# TransientsWiring.net
KiCad netlist of a schematic drawn in EAGLE
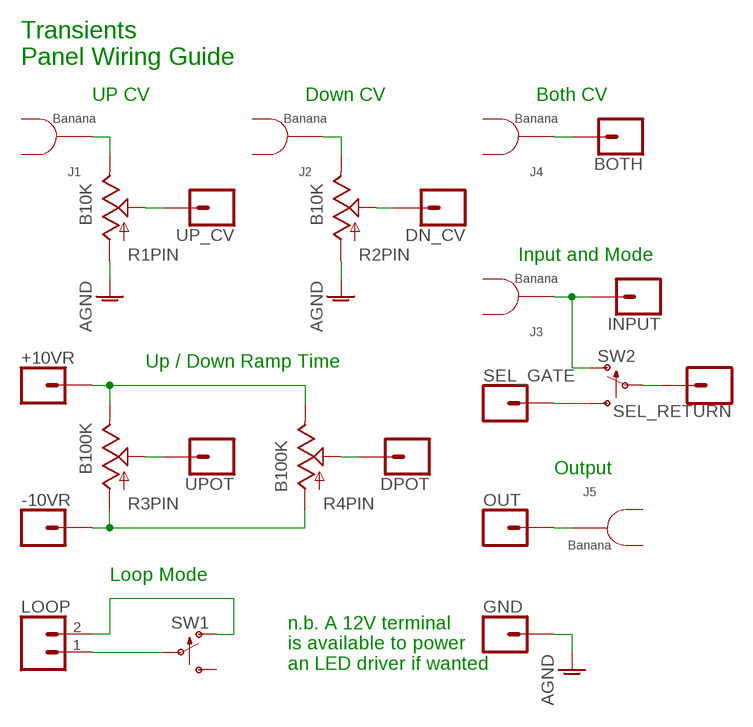
[diagram p0: schematic, sheet 1]

(export (version "E")
  (design (tool "Eeschema 10.0.6"))
  (components
    (comp (ref "+10VR")
      (value "1XWIREPAD")
      (footprint "eagle-import:1X01")
      (libsource (lib "eagle-import") (part "1XWIREPAD"))
    )
    (comp (ref "-10VR")
      (value "1XWIREPAD")
      (footprint "eagle-import:1X01")
      (libsource (lib "eagle-import") (part "1XWIREPAD"))
    )
    (comp (ref "BOTH")
      (value "1XWIREPAD")
      (footprint "eagle-import:1X01")
      (libsource (lib "eagle-import") (part "1XWIREPAD"))
    )
    (comp (ref "DN_CV")
      (value "1XWIREPAD")
      (footprint "eagle-import:1X01")
      (libsource (lib "eagle-import") (part "1XWIREPAD"))
    )
    (comp (ref "DPOT")
      (value "1XWIREPAD")
      (footprint "eagle-import:1X01")
      (libsource (lib "eagle-import") (part "1XWIREPAD"))
    )
    (comp (ref "GND")
      (value "1XWIREPAD")
      (footprint "eagle-import:1X01")
      (libsource (lib "eagle-import") (part "1XWIREPAD"))
    )
    (comp (ref "INPUT")
      (value "1XWIREPAD")
      (footprint "eagle-import:1X01")
      (libsource (lib "eagle-import") (part "1XWIREPAD"))
    )
    (comp (ref "J1")
      (value "BANANA_SOCKET_PAD")
      (footprint "eagle-import:BANANA_PCB_PAD")
      (libsource (lib "eagle-import") (part "BANANA_SOCKET_PAD"))
    )
    (comp (ref "J2")
      (value "BANANA_SOCKET_PAD")
      (footprint "eagle-import:BANANA_PCB_PAD")
      (libsource (lib "eagle-import") (part "BANANA_SOCKET_PAD"))
    )
    (comp (ref "J3")
      (value "BANANA_SOCKET_PAD")
      (footprint "eagle-import:BANANA_PCB_PAD")
      (libsource (lib "eagle-import") (part "BANANA_SOCKET_PAD"))
    )
    (comp (ref "J4")
      (value "BANANA_SOCKET_PAD")
      (footprint "eagle-import:BANANA_PCB_PAD")
      (libsource (lib "eagle-import") (part "BANANA_SOCKET_PAD"))
    )
    (comp (ref "J5")
      (value "BANANA_SOCKET_PAD")
      (footprint "eagle-import:BANANA_PCB_PAD")
      (libsource (lib "eagle-import") (part "BANANA_SOCKET_PAD"))
    )
    (comp (ref "LOOP")
      (value "2XWIREPAD")
      (footprint "eagle-import:1X02")
      (libsource (lib "eagle-import") (part "2XWIREPAD"))
    )
    (comp (ref "OUT")
      (value "1XWIREPAD")
      (footprint "eagle-import:1X01")
      (libsource (lib "eagle-import") (part "1XWIREPAD"))
    )
    (comp (ref "R1")
      (value "B10K")
      (footprint "eagle-import:ALPHA_RV09_9MMPOT")
      (libsource (lib "eagle-import") (part "POTENTIOMETER"))
    )
    (comp (ref "R2")
      (value "B10K")
      (footprint "eagle-import:ALPHA_RV09_9MMPOT")
      (libsource (lib "eagle-import") (part "POTENTIOMETER"))
    )
    (comp (ref "R3")
      (value "B100K")
      (footprint "eagle-import:ALPHA_RV09_9MMPOT")
      (libsource (lib "eagle-import") (part "POTENTIOMETER"))
    )
    (comp (ref "R4")
      (value "B100K")
      (footprint "eagle-import:ALPHA_RV09_9MMPOT")
      (libsource (lib "eagle-import") (part "POTENTIOMETER"))
    )
    (comp (ref "SEL_GATE")
      (value "1XWIREPAD")
      (footprint "eagle-import:1X01")
      (libsource (lib "eagle-import") (part "1XWIREPAD"))
    )
    (comp (ref "SEL_RETURN")
      (value "1XWIREPAD")
      (footprint "eagle-import:1X01")
      (libsource (lib "eagle-import") (part "1XWIREPAD"))
    )
    (comp (ref "SW1")
      (value "SPDT_SWITCHDW1")
      (footprint "eagle-import:MICRODPDT-DW1")
      (libsource (lib "eagle-import") (part "SPDT_SWITCHDW1"))
    )
    (comp (ref "SW2")
      (value "SPDT_SWITCHDW1")
      (footprint "eagle-import:MICRODPDT-DW1")
      (libsource (lib "eagle-import") (part "SPDT_SWITCHDW1"))
    )
    (comp (ref "UPOT")
      (value "1XWIREPAD")
      (footprint "eagle-import:1X01")
      (libsource (lib "eagle-import") (part "1XWIREPAD"))
    )
    (comp (ref "UP_CV")
      (value "1XWIREPAD")
      (footprint "eagle-import:1X01")
      (libsource (lib "eagle-import") (part "1XWIREPAD"))
    )
  )
  (nets
    (net (code "1") (name "AGND") (class "Default")
      (node (ref "GND") (pin "1") (pinfunction "1_1") (pintype "passive"))
      (node (ref "R1") (pin "C1") (pinfunction "A_C1") (pintype "passive"))
      (node (ref "R2") (pin "C1") (pinfunction "A_C1") (pintype "passive"))
    )
    (net (code "2") (name "Net-(J1-P$1)") (class "Default")
      (node (ref "J1") (pin "P$2") (pinfunction "P$1_P$2") (pintype "bidirectional"))
      (node (ref "R1") (pin "C3") (pinfunction "B_C3") (pintype "passive"))
    )
    (net (code "3") (name "Net-(J2-P$1)") (class "Default")
      (node (ref "J2") (pin "P$2") (pinfunction "P$1_P$2") (pintype "bidirectional"))
      (node (ref "R2") (pin "C3") (pinfunction "B_C3") (pintype "passive"))
    )
    (net (code "4") (name "Net-(J3-P$1)") (class "Default")
      (node (ref "INPUT") (pin "1") (pinfunction "1_1") (pintype "passive"))
      (node (ref "J3") (pin "P$2") (pinfunction "P$1_P$2") (pintype "bidirectional"))
      (node (ref "SW2") (pin "C1") (pinfunction "O_C1") (pintype "passive"))
    )
    (net (code "5") (name "Net-(J4-P$1)") (class "Default")
      (node (ref "BOTH") (pin "1") (pinfunction "1_1") (pintype "passive"))
      (node (ref "J4") (pin "P$2") (pinfunction "P$1_P$2") (pintype "bidirectional"))
    )
    (net (code "6") (name "Net-(J5-P$1)") (class "Default")
      (node (ref "J5") (pin "P$2") (pinfunction "P$1_P$2") (pintype "bidirectional"))
      (node (ref "OUT") (pin "1") (pinfunction "1_1") (pintype "passive"))
    )
    (net (code "7") (name "Net-(R1B-W)") (class "Default")
      (node (ref "R1") (pin "C2") (pinfunction "W_C2") (pintype "passive"))
      (node (ref "UP_CV") (pin "1") (pinfunction "1_1") (pintype "passive"))
    )
    (net (code "8") (name "Net-(R2B-W)") (class "Default")
      (node (ref "DN_CV") (pin "1") (pinfunction "1_1") (pintype "passive"))
      (node (ref "R2") (pin "C2") (pinfunction "W_C2") (pintype "passive"))
    )
    (net (code "9") (name "Net-(R3B-A)") (class "Default")
      (node (ref "-10VR") (pin "1") (pinfunction "1_1") (pintype "passive"))
      (node (ref "R3") (pin "C1") (pinfunction "A_C1") (pintype "passive"))
      (node (ref "R4") (pin "C1") (pinfunction "A_C1") (pintype "passive"))
    )
    (net (code "10") (name "Net-(R3B-B)") (class "Default")
      (node (ref "+10VR") (pin "1") (pinfunction "1_1") (pintype "passive"))
      (node (ref "R3") (pin "C3") (pinfunction "B_C3") (pintype "passive"))
      (node (ref "R4") (pin "C3") (pinfunction "B_C3") (pintype "passive"))
    )
    (net (code "11") (name "Net-(R3B-W)") (class "Default")
      (node (ref "R3") (pin "C2") (pinfunction "W_C2") (pintype "passive"))
      (node (ref "UPOT") (pin "1") (pinfunction "1_1") (pintype "passive"))
    )
    (net (code "12") (name "Net-(R4B-W)") (class "Default")
      (node (ref "DPOT") (pin "1") (pinfunction "1_1") (pintype "passive"))
      (node (ref "R4") (pin "C2") (pinfunction "W_C2") (pintype "passive"))
    )
    (net (code "13") (name "Net-(SW1-O)") (class "Default")
      (node (ref "LOOP") (pin "2") (pinfunction "2_2") (pintype "passive"))
      (node (ref "SW1") (pin "C1") (pinfunction "O_C1") (pintype "passive"))
    )
    (net (code "14") (name "Net-(SW1-P)") (class "Default")
      (node (ref "LOOP") (pin "1") (pinfunction "1_1") (pintype "passive"))
      (node (ref "SW1") (pin "C2") (pinfunction "P_C2") (pintype "passive"))
    )
    (net (code "15") (name "Net-(SW2-P)") (class "Default")
      (node (ref "SEL_RETURN") (pin "1") (pinfunction "1_1") (pintype "passive"))
      (node (ref "SW2") (pin "C2") (pinfunction "P_C2") (pintype "passive"))
    )
    (net (code "16") (name "Net-(SW2-S)") (class "Default")
      (node (ref "SEL_GATE") (pin "1") (pinfunction "1_1") (pintype "passive"))
      (node (ref "SW2") (pin "C3") (pinfunction "S_C3") (pintype "passive"))
    )
    (net (code "17") (name "unconnected-(SW1-S-PadC3)") (class "Default")
      (node (ref "SW1") (pin "C3") (pinfunction "S_C3") (pintype "passive"))
    )
  )
)
